# display.net
KiCad netlist of a schematic drawn in EAGLE
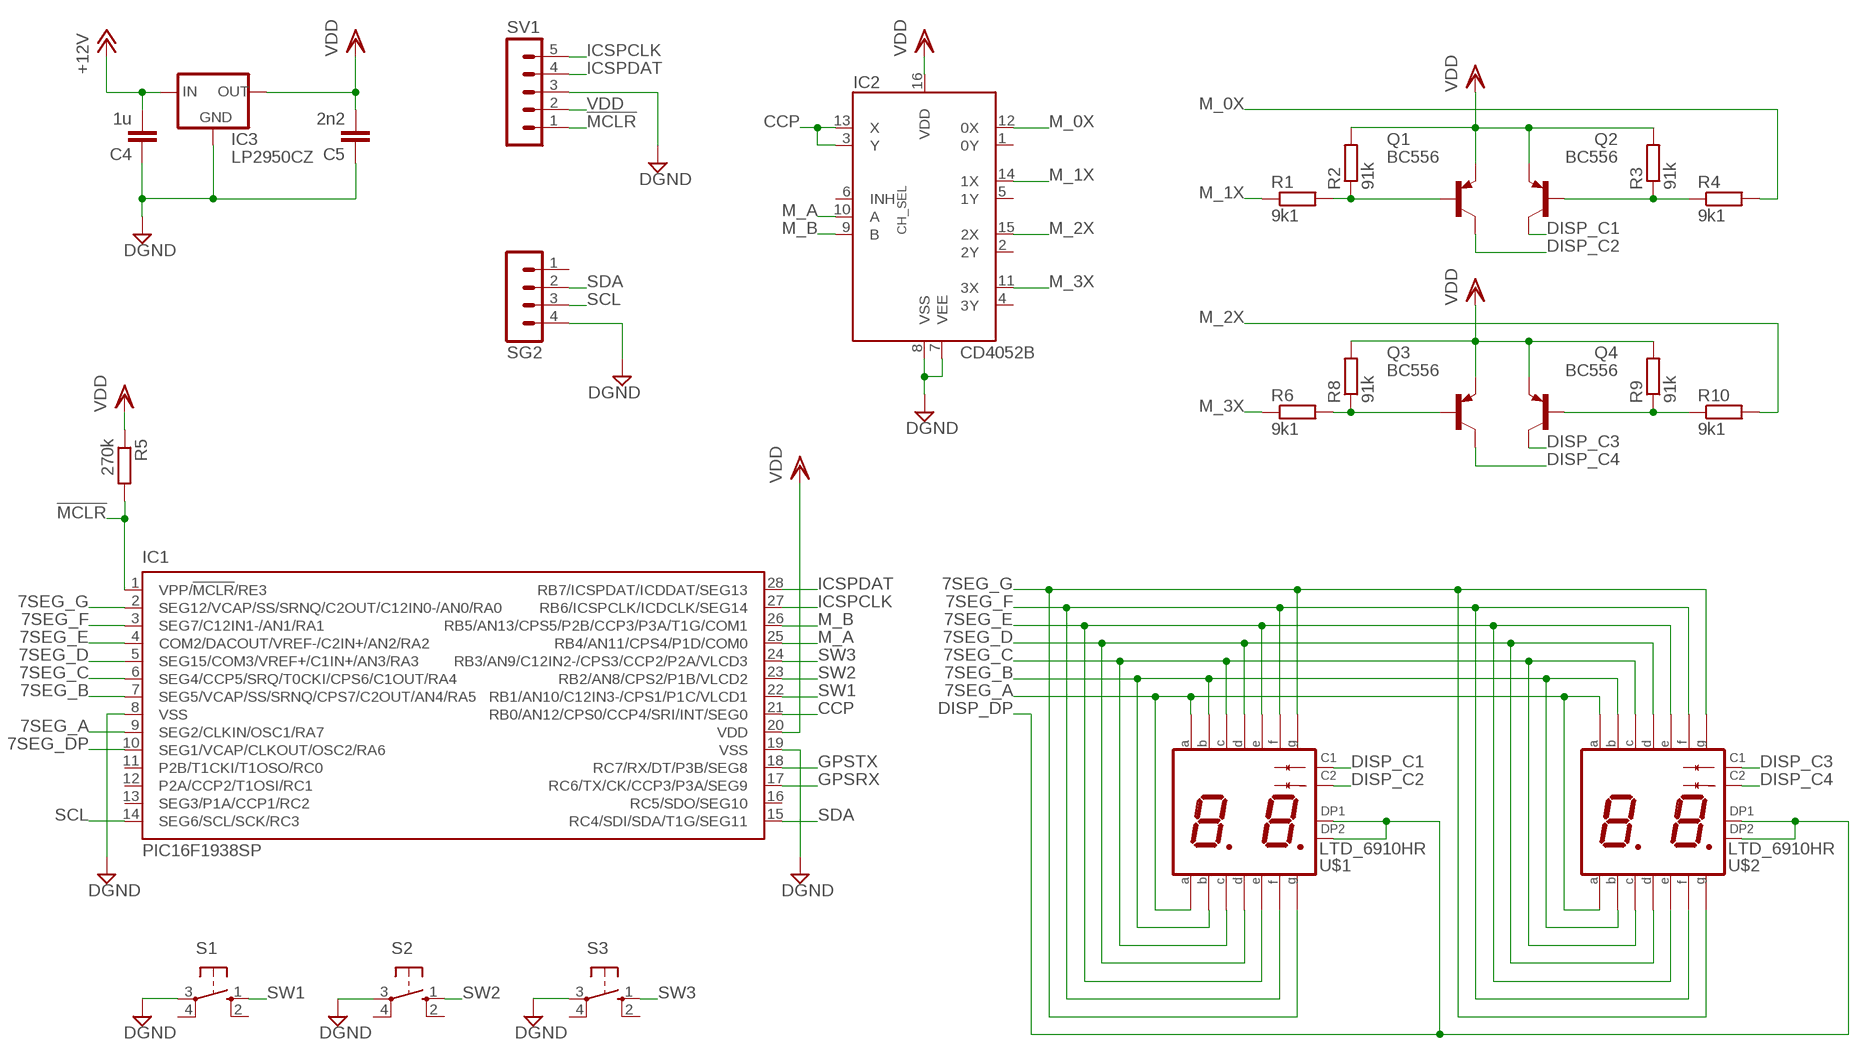
[diagram p0: schematic, sheet 1]

(export (version "E")
  (design (tool "Eeschema 10.0.6"))
  (components
    (comp (ref "C4")
      (value "1u")
      (footprint "eagle-import:C5B2.5")
      (libsource (lib "eagle-import") (part "C5/2.5"))
    )
    (comp (ref "C5")
      (value "2n2")
      (footprint "eagle-import:C5B2.5")
      (libsource (lib "eagle-import") (part "C5/2.5"))
    )
    (comp (ref "IC1")
      (value "PIC16F1938SP")
      (footprint "eagle-import:DIL28-3")
      (fields (field (name "MPN") "PIC16F1938-I/SP"))
      (libsource (lib "eagle-import") (part "PIC16F19SP38"))
    )
    (comp (ref "IC2")
      (value "CD4052B")
      (footprint "eagle-import:DIL16")
      (libsource (lib "eagle-import") (part "CD4052B"))
    )
    (comp (ref "IC3")
      (value "LP2950CZ")
      (footprint "eagle-import:TO92")
      (libsource (lib "eagle-import") (part "LP2950?CZ-5.0"))
    )
    (comp (ref "Q1")
      (value "BC556")
      (footprint "eagle-import:TO92-EBC")
      (libsource (lib "eagle-import") (part "BC556"))
    )
    (comp (ref "Q2")
      (value "BC556")
      (footprint "eagle-import:TO92-EBC")
      (libsource (lib "eagle-import") (part "BC556"))
    )
    (comp (ref "Q3")
      (value "BC556")
      (footprint "eagle-import:TO92-EBC")
      (libsource (lib "eagle-import") (part "BC556"))
    )
    (comp (ref "Q4")
      (value "BC556")
      (footprint "eagle-import:TO92-EBC")
      (libsource (lib "eagle-import") (part "BC556"))
    )
    (comp (ref "R1")
      (value "9k1")
      (footprint "eagle-import:0204_5")
      (libsource (lib "eagle-import") (part "R-EU_0204/5"))
    )
    (comp (ref "R2")
      (value "91k")
      (footprint "eagle-import:0204_5")
      (libsource (lib "eagle-import") (part "R-EU_0204/5"))
    )
    (comp (ref "R3")
      (value "91k")
      (footprint "eagle-import:0204_5")
      (libsource (lib "eagle-import") (part "R-EU_0204/5"))
    )
    (comp (ref "R4")
      (value "9k1")
      (footprint "eagle-import:0204_5")
      (libsource (lib "eagle-import") (part "R-EU_0204/5"))
    )
    (comp (ref "R5")
      (value "270k")
      (footprint "eagle-import:M1206")
      (libsource (lib "eagle-import") (part "R-EU_M1206"))
    )
    (comp (ref "R6")
      (value "9k1")
      (footprint "eagle-import:0204_5")
      (libsource (lib "eagle-import") (part "R-EU_0204/5"))
    )
    (comp (ref "R8")
      (value "91k")
      (footprint "eagle-import:0204_5")
      (libsource (lib "eagle-import") (part "R-EU_0204/5"))
    )
    (comp (ref "R9")
      (value "91k")
      (footprint "eagle-import:0204_5")
      (libsource (lib "eagle-import") (part "R-EU_0204/5"))
    )
    (comp (ref "R10")
      (value "9k1")
      (footprint "eagle-import:0204_5")
      (libsource (lib "eagle-import") (part "R-EU_0204/5"))
    )
    (comp (ref "S1")
      (value "10-XX")
      (footprint "eagle-import:B3F-10XX")
      (fields (field (name "MPN") "B3F-1000"))
      (libsource (lib "eagle-import") (part "10-XX"))
    )
    (comp (ref "S2")
      (value "10-XX")
      (footprint "eagle-import:B3F-10XX")
      (fields (field (name "MPN") "B3F-1000"))
      (libsource (lib "eagle-import") (part "10-XX"))
    )
    (comp (ref "S3")
      (value "10-XX")
      (footprint "eagle-import:B3F-10XX")
      (fields (field (name "MPN") "B3F-1000"))
      (libsource (lib "eagle-import") (part "10-XX"))
    )
    (comp (ref "SG2")
      (value "MA04-1")
      (footprint "eagle-import:MA04-1")
      (libsource (lib "eagle-import") (part "MA04-1"))
    )
    (comp (ref "SV1")
      (value "MA05-1")
      (footprint "eagle-import:MA05-1")
      (libsource (lib "eagle-import") (part "MA05-1"))
    )
    (comp (ref "U$1")
      (value "LTD_6910HR")
      (footprint "eagle-import:7-SEG-LED-DUAL")
      (libsource (lib "eagle-import") (part "LTD_6910HR"))
    )
    (comp (ref "U$2")
      (value "LTD_6910HR")
      (footprint "eagle-import:7-SEG-LED-DUAL")
      (libsource (lib "eagle-import") (part "LTD_6910HR"))
    )
  )
  (nets
    (net (code "1") (name "+12V") (class "Default")
      (node (ref "C4") (pin "2") (pinfunction "2_2") (pintype "passive"))
      (node (ref "IC3") (pin "3") (pinfunction "IN_3") (pintype "input"))
    )
    (net (code "2") (name "/7SEG_A") (class "Default")
      (node (ref "IC1") (pin "9") (pinfunction "SEG2/CLKIN/OSC1/RA7_9") (pintype "bidirectional"))
      (node (ref "U$1") (pin "P$11") (pinfunction "A2_P$11") (pintype "passive"))
      (node (ref "U$1") (pin "P$16") (pinfunction "A1_P$16") (pintype "passive"))
      (node (ref "U$2") (pin "P$11") (pinfunction "A2_P$11") (pintype "passive"))
      (node (ref "U$2") (pin "P$16") (pinfunction "A1_P$16") (pintype "passive"))
    )
    (net (code "3") (name "/7SEG_B") (class "Default")
      (node (ref "IC1") (pin "7") (pinfunction "SEG5/VCAP/SS/SRNQ/CPS7/C2OUT/AN4/RA5_7") (pintype "bidirectional"))
      (node (ref "U$1") (pin "P$10") (pinfunction "B2_P$10") (pintype "passive"))
      (node (ref "U$1") (pin "P$15") (pinfunction "B1_P$15") (pintype "passive"))
      (node (ref "U$2") (pin "P$10") (pinfunction "B2_P$10") (pintype "passive"))
      (node (ref "U$2") (pin "P$15") (pinfunction "B1_P$15") (pintype "passive"))
    )
    (net (code "4") (name "/7SEG_C") (class "Default")
      (node (ref "IC1") (pin "6") (pinfunction "SEG4/CCP5/SRQ/T0CKI/CPS6/C1OUT/RA4_6") (pintype "bidirectional"))
      (node (ref "U$1") (pin "P$3") (pinfunction "C1_P$3") (pintype "passive"))
      (node (ref "U$1") (pin "P$8") (pinfunction "C2_P$8") (pintype "passive"))
      (node (ref "U$2") (pin "P$3") (pinfunction "C1_P$3") (pintype "passive"))
      (node (ref "U$2") (pin "P$8") (pinfunction "C2_P$8") (pintype "passive"))
    )
    (net (code "5") (name "/7SEG_D") (class "Default")
      (node (ref "IC1") (pin "5") (pinfunction "SEG15/COM3/VREF+/C1IN+/AN3/RA3_5") (pintype "bidirectional"))
      (node (ref "U$1") (pin "P$2") (pinfunction "D1_P$2") (pintype "passive"))
      (node (ref "U$1") (pin "P$6") (pinfunction "D2_P$6") (pintype "passive"))
      (node (ref "U$2") (pin "P$2") (pinfunction "D1_P$2") (pintype "passive"))
      (node (ref "U$2") (pin "P$6") (pinfunction "D2_P$6") (pintype "passive"))
    )
    (net (code "6") (name "/7SEG_DP") (class "Default")
      (node (ref "IC1") (pin "10") (pinfunction "SEG1/VCAP/CLKOUT/OSC2/RA6_10") (pintype "bidirectional"))
    )
    (net (code "7") (name "/7SEG_E") (class "Default")
      (node (ref "IC1") (pin "4") (pinfunction "COM2/DACOUT/VREF-/C2IN+/AN2/RA2_4") (pintype "bidirectional"))
      (node (ref "U$1") (pin "P$1") (pinfunction "E1_P$1") (pintype "passive"))
      (node (ref "U$1") (pin "P$5") (pinfunction "E2_P$5") (pintype "passive"))
      (node (ref "U$2") (pin "P$1") (pinfunction "E1_P$1") (pintype "passive"))
      (node (ref "U$2") (pin "P$5") (pinfunction "E2_P$5") (pintype "passive"))
    )
    (net (code "8") (name "/7SEG_F") (class "Default")
      (node (ref "IC1") (pin "3") (pinfunction "SEG7/C12IN1-/AN1/RA1_3") (pintype "bidirectional"))
      (node (ref "U$1") (pin "P$12") (pinfunction "F2_P$12") (pintype "passive"))
      (node (ref "U$1") (pin "P$18") (pinfunction "F1_P$18") (pintype "passive"))
      (node (ref "U$2") (pin "P$12") (pinfunction "F2_P$12") (pintype "passive"))
      (node (ref "U$2") (pin "P$18") (pinfunction "F1_P$18") (pintype "passive"))
    )
    (net (code "9") (name "/7SEG_G") (class "Default")
      (node (ref "IC1") (pin "2") (pinfunction "SEG12/VCAP/SS/SRNQ/C2OUT/C12IN0-/AN0/RA0_2") (pintype "bidirectional"))
      (node (ref "U$1") (pin "P$17") (pinfunction "G1_P$17") (pintype "passive"))
      (node (ref "U$1") (pin "P$7") (pinfunction "G2_P$7") (pintype "passive"))
      (node (ref "U$2") (pin "P$17") (pinfunction "G1_P$17") (pintype "passive"))
      (node (ref "U$2") (pin "P$7") (pinfunction "G2_P$7") (pintype "passive"))
    )
    (net (code "10") (name "/CCP") (class "Default")
      (node (ref "IC1") (pin "21") (pinfunction "RB0/AN12/CPS0/CCP4/SRI/INT/SEG0_21") (pintype "bidirectional"))
      (node (ref "IC2") (pin "13") (pinfunction "X_13") (pintype "bidirectional"))
      (node (ref "IC2") (pin "3") (pinfunction "Y_3") (pintype "bidirectional"))
    )
    (net (code "11") (name "/DISP_C1") (class "Default")
      (node (ref "Q2") (pin "C") (pinfunction "C_C") (pintype "passive"))
      (node (ref "U$1") (pin "P$14") (pinfunction "C_P$14") (pintype "passive"))
    )
    (net (code "12") (name "/DISP_C2") (class "Default")
      (node (ref "Q1") (pin "C") (pinfunction "C_C") (pintype "passive"))
      (node (ref "U$1") (pin "P$13") (pinfunction "C_P$13") (pintype "passive"))
    )
    (net (code "13") (name "/DISP_C3") (class "Default")
      (node (ref "Q4") (pin "C") (pinfunction "C_C") (pintype "passive"))
      (node (ref "U$2") (pin "P$14") (pinfunction "C_P$14") (pintype "passive"))
    )
    (net (code "14") (name "/DISP_C4") (class "Default")
      (node (ref "Q3") (pin "C") (pinfunction "C_C") (pintype "passive"))
      (node (ref "U$2") (pin "P$13") (pinfunction "C_P$13") (pintype "passive"))
    )
    (net (code "15") (name "/DISP_DP") (class "Default")
      (node (ref "U$1") (pin "P$4") (pinfunction "DP_P$4") (pintype "passive"))
      (node (ref "U$1") (pin "P$9") (pinfunction "DP_P$9") (pintype "passive"))
      (node (ref "U$2") (pin "P$4") (pinfunction "DP_P$4") (pintype "passive"))
      (node (ref "U$2") (pin "P$9") (pinfunction "DP_P$9") (pintype "passive"))
    )
    (net (code "16") (name "/GPSRX") (class "Default")
      (node (ref "IC1") (pin "17") (pinfunction "RC6/TX/CK/CCP3/P3A/SEG9_17") (pintype "bidirectional"))
    )
    (net (code "17") (name "/GPSTX") (class "Default")
      (node (ref "IC1") (pin "18") (pinfunction "RC7/RX/DT/P3B/SEG8_18") (pintype "bidirectional"))
    )
    (net (code "18") (name "/ICSPCLK") (class "Default")
      (node (ref "IC1") (pin "27") (pinfunction "RB6/ICSPCLK/ICDCLK/SEG14_27") (pintype "bidirectional"))
      (node (ref "SV1") (pin "5") (pinfunction "5_5") (pintype "passive"))
    )
    (net (code "19") (name "/ICSPDAT") (class "Default")
      (node (ref "IC1") (pin "28") (pinfunction "RB7/ICSPDAT/ICDDAT/SEG13_28") (pintype "bidirectional"))
      (node (ref "SV1") (pin "4") (pinfunction "4_4") (pintype "passive"))
    )
    (net (code "20") (name "/M_0X") (class "Default")
      (node (ref "IC2") (pin "12") (pinfunction "0X_12") (pintype "bidirectional"))
      (node (ref "R4") (pin "2") (pinfunction "2_2") (pintype "passive"))
    )
    (net (code "21") (name "/M_1X") (class "Default")
      (node (ref "IC2") (pin "14") (pinfunction "1X_14") (pintype "bidirectional"))
      (node (ref "R1") (pin "1") (pinfunction "1_1") (pintype "passive"))
    )
    (net (code "22") (name "/M_2X") (class "Default")
      (node (ref "IC2") (pin "15") (pinfunction "2X_15") (pintype "bidirectional"))
      (node (ref "R10") (pin "2") (pinfunction "2_2") (pintype "passive"))
    )
    (net (code "23") (name "/M_3X") (class "Default")
      (node (ref "IC2") (pin "11") (pinfunction "3X_11") (pintype "bidirectional"))
      (node (ref "R6") (pin "1") (pinfunction "1_1") (pintype "passive"))
    )
    (net (code "24") (name "/M_A") (class "Default")
      (node (ref "IC1") (pin "25") (pinfunction "RB4/AN11/CPS4/P1D/COM0_25") (pintype "bidirectional"))
      (node (ref "IC2") (pin "10") (pinfunction "A_10") (pintype "bidirectional"))
    )
    (net (code "25") (name "/M_B") (class "Default")
      (node (ref "IC1") (pin "26") (pinfunction "RB5/AN13/CPS5/P2B/CCP3/P3A/T1G/COM1_26") (pintype "bidirectional"))
      (node (ref "IC2") (pin "9") (pinfunction "B_9") (pintype "bidirectional"))
    )
    (net (code "26") (name "/SCL") (class "Default")
      (node (ref "IC1") (pin "14") (pinfunction "SEG6/SCL/SCK/RC3_14") (pintype "bidirectional"))
      (node (ref "SG2") (pin "3") (pinfunction "3_3") (pintype "passive"))
    )
    (net (code "27") (name "/SDA") (class "Default")
      (node (ref "IC1") (pin "15") (pinfunction "RC4/SDI/SDA/T1G/SEG11_15") (pintype "bidirectional"))
      (node (ref "SG2") (pin "2") (pinfunction "2_2") (pintype "passive"))
    )
    (net (code "28") (name "/SW1") (class "Default")
      (node (ref "IC1") (pin "22") (pinfunction "RB1/AN10/C12IN3-/CPS1/P1C/VLCD1_22") (pintype "bidirectional"))
      (node (ref "S1") (pin "1") (pinfunction "S_1") (pintype "passive"))
    )
    (net (code "29") (name "/SW2") (class "Default")
      (node (ref "IC1") (pin "23") (pinfunction "RB2/AN8/CPS2/P1B/VLCD2_23") (pintype "bidirectional"))
      (node (ref "S2") (pin "1") (pinfunction "S_1") (pintype "passive"))
    )
    (net (code "30") (name "/SW3") (class "Default")
      (node (ref "IC1") (pin "24") (pinfunction "RB3/AN9/C12IN2-/CPS3/CCP2/P2A/VLCD3_24") (pintype "bidirectional"))
      (node (ref "S3") (pin "1") (pinfunction "S_1") (pintype "passive"))
    )
    (net (code "31") (name "/~{MCLR}") (class "Default")
      (node (ref "IC1") (pin "1") (pinfunction "VPP/~{MCLR}/RE3_1") (pintype "input"))
      (node (ref "R5") (pin "2") (pinfunction "2_2") (pintype "passive"))
      (node (ref "SV1") (pin "1") (pinfunction "1_1") (pintype "passive"))
    )
    (net (code "32") (name "DGND") (class "Default")
      (node (ref "C4") (pin "1") (pinfunction "1_1") (pintype "passive"))
      (node (ref "C5") (pin "1") (pinfunction "1_1") (pintype "passive"))
      (node (ref "IC1") (pin "19") (pinfunction "VSS_19") (pintype "power_in"))
      (node (ref "IC1") (pin "8") (pinfunction "VSS_8") (pintype "power_in"))
      (node (ref "IC2") (pin "7") (pinfunction "VEE_7") (pintype "bidirectional"))
      (node (ref "IC2") (pin "8") (pinfunction "VSS_8") (pintype "bidirectional"))
      (node (ref "IC3") (pin "2") (pinfunction "GND_2") (pintype "input"))
      (node (ref "S1") (pin "3") (pinfunction "P_3") (pintype "passive"))
      (node (ref "S2") (pin "3") (pinfunction "P_3") (pintype "passive"))
      (node (ref "S3") (pin "3") (pinfunction "P_3") (pintype "passive"))
      (node (ref "SG2") (pin "4") (pinfunction "4_4") (pintype "passive"))
      (node (ref "SV1") (pin "3") (pinfunction "3_3") (pintype "passive"))
    )
    (net (code "33") (name "Net-(Q1-PadB)") (class "Default")
      (node (ref "Q1") (pin "B") (pinfunction "B_B") (pintype "passive"))
      (node (ref "R1") (pin "2") (pinfunction "2_2") (pintype "passive"))
      (node (ref "R2") (pin "1") (pinfunction "1_1") (pintype "passive"))
    )
    (net (code "34") (name "Net-(Q2-PadB)") (class "Default")
      (node (ref "Q2") (pin "B") (pinfunction "B_B") (pintype "passive"))
      (node (ref "R3") (pin "1") (pinfunction "1_1") (pintype "passive"))
      (node (ref "R4") (pin "1") (pinfunction "1_1") (pintype "passive"))
    )
    (net (code "35") (name "Net-(Q3-PadB)") (class "Default")
      (node (ref "Q3") (pin "B") (pinfunction "B_B") (pintype "passive"))
      (node (ref "R6") (pin "2") (pinfunction "2_2") (pintype "passive"))
      (node (ref "R8") (pin "1") (pinfunction "1_1") (pintype "passive"))
    )
    (net (code "36") (name "Net-(Q4-PadB)") (class "Default")
      (node (ref "Q4") (pin "B") (pinfunction "B_B") (pintype "passive"))
      (node (ref "R10") (pin "1") (pinfunction "1_1") (pintype "passive"))
      (node (ref "R9") (pin "1") (pinfunction "1_1") (pintype "passive"))
    )
    (net (code "37") (name "VDD") (class "Default")
      (node (ref "C5") (pin "2") (pinfunction "2_2") (pintype "passive"))
      (node (ref "IC1") (pin "20") (pinfunction "VDD_20") (pintype "power_in"))
      (node (ref "IC2") (pin "16") (pinfunction "VDD_16") (pintype "bidirectional"))
      (node (ref "IC3") (pin "1") (pinfunction "OUT_1") (pintype "passive"))
      (node (ref "Q1") (pin "E") (pinfunction "E_E") (pintype "passive"))
      (node (ref "Q2") (pin "E") (pinfunction "E_E") (pintype "passive"))
      (node (ref "Q3") (pin "E") (pinfunction "E_E") (pintype "passive"))
      (node (ref "Q4") (pin "E") (pinfunction "E_E") (pintype "passive"))
      (node (ref "R2") (pin "2") (pinfunction "2_2") (pintype "passive"))
      (node (ref "R3") (pin "2") (pinfunction "2_2") (pintype "passive"))
      (node (ref "R5") (pin "1") (pinfunction "1_1") (pintype "passive"))
      (node (ref "R8") (pin "2") (pinfunction "2_2") (pintype "passive"))
      (node (ref "R9") (pin "2") (pinfunction "2_2") (pintype "passive"))
      (node (ref "SV1") (pin "2") (pinfunction "2_2") (pintype "passive"))
    )
    (net (code "38") (name "unconnected-(IC1-P2A{slash}CCP2{slash}T1OSI{slash}RC1-Pad12)") (class "Default")
      (node (ref "IC1") (pin "12") (pinfunction "P2A/CCP2/T1OSI/RC1_12") (pintype "bidirectional"))
    )
    (net (code "39") (name "unconnected-(IC1-P2B{slash}T1CKI{slash}T1OSO{slash}RC0-Pad11)") (class "Default")
      (node (ref "IC1") (pin "11") (pinfunction "P2B/T1CKI/T1OSO/RC0_11") (pintype "bidirectional"))
    )
    (net (code "40") (name "unconnected-(IC1-RC5{slash}SDO{slash}SEG10-Pad16)") (class "Default")
      (node (ref "IC1") (pin "16") (pinfunction "RC5/SDO/SEG10_16") (pintype "bidirectional"))
    )
    (net (code "41") (name "unconnected-(IC1-SEG3{slash}P1A{slash}CCP1{slash}RC2-Pad13)") (class "Default")
      (node (ref "IC1") (pin "13") (pinfunction "SEG3/P1A/CCP1/RC2_13") (pintype "bidirectional"))
    )
    (net (code "42") (name "unconnected-(IC2-0Y-Pad1)") (class "Default")
      (node (ref "IC2") (pin "1") (pinfunction "0Y_1") (pintype "bidirectional"))
    )
    (net (code "43") (name "unconnected-(IC2-1Y-Pad5)") (class "Default")
      (node (ref "IC2") (pin "5") (pinfunction "1Y_5") (pintype "bidirectional"))
    )
    (net (code "44") (name "unconnected-(IC2-2Y-Pad2)") (class "Default")
      (node (ref "IC2") (pin "2") (pinfunction "2Y_2") (pintype "bidirectional"))
    )
    (net (code "45") (name "unconnected-(IC2-3Y-Pad4)") (class "Default")
      (node (ref "IC2") (pin "4") (pinfunction "3Y_4") (pintype "bidirectional"))
    )
    (net (code "46") (name "unconnected-(IC2-INH-Pad6)") (class "Default")
      (node (ref "IC2") (pin "6") (pinfunction "INH_6") (pintype "bidirectional"))
    )
    (net (code "47") (name "unconnected-(S1-P1-Pad4)") (class "Default")
      (node (ref "S1") (pin "4") (pinfunction "P1_4") (pintype "passive"))
    )
    (net (code "48") (name "unconnected-(S1-S1-Pad2)") (class "Default")
      (node (ref "S1") (pin "2") (pinfunction "S1_2") (pintype "passive"))
    )
    (net (code "49") (name "unconnected-(S2-P1-Pad4)") (class "Default")
      (node (ref "S2") (pin "4") (pinfunction "P1_4") (pintype "passive"))
    )
    (net (code "50") (name "unconnected-(S2-S1-Pad2)") (class "Default")
      (node (ref "S2") (pin "2") (pinfunction "S1_2") (pintype "passive"))
    )
    (net (code "51") (name "unconnected-(S3-P1-Pad4)") (class "Default")
      (node (ref "S3") (pin "4") (pinfunction "P1_4") (pintype "passive"))
    )
    (net (code "52") (name "unconnected-(S3-S1-Pad2)") (class "Default")
      (node (ref "S3") (pin "2") (pinfunction "S1_2") (pintype "passive"))
    )
    (net (code "53") (name "unconnected-(SG2-Pad1)") (class "Default")
      (node (ref "SG2") (pin "1") (pinfunction "1_1") (pintype "passive"))
    )
  )
)
